# mouseHatbiggertest.net
KiCad netlist of a schematic drawn in EAGLE
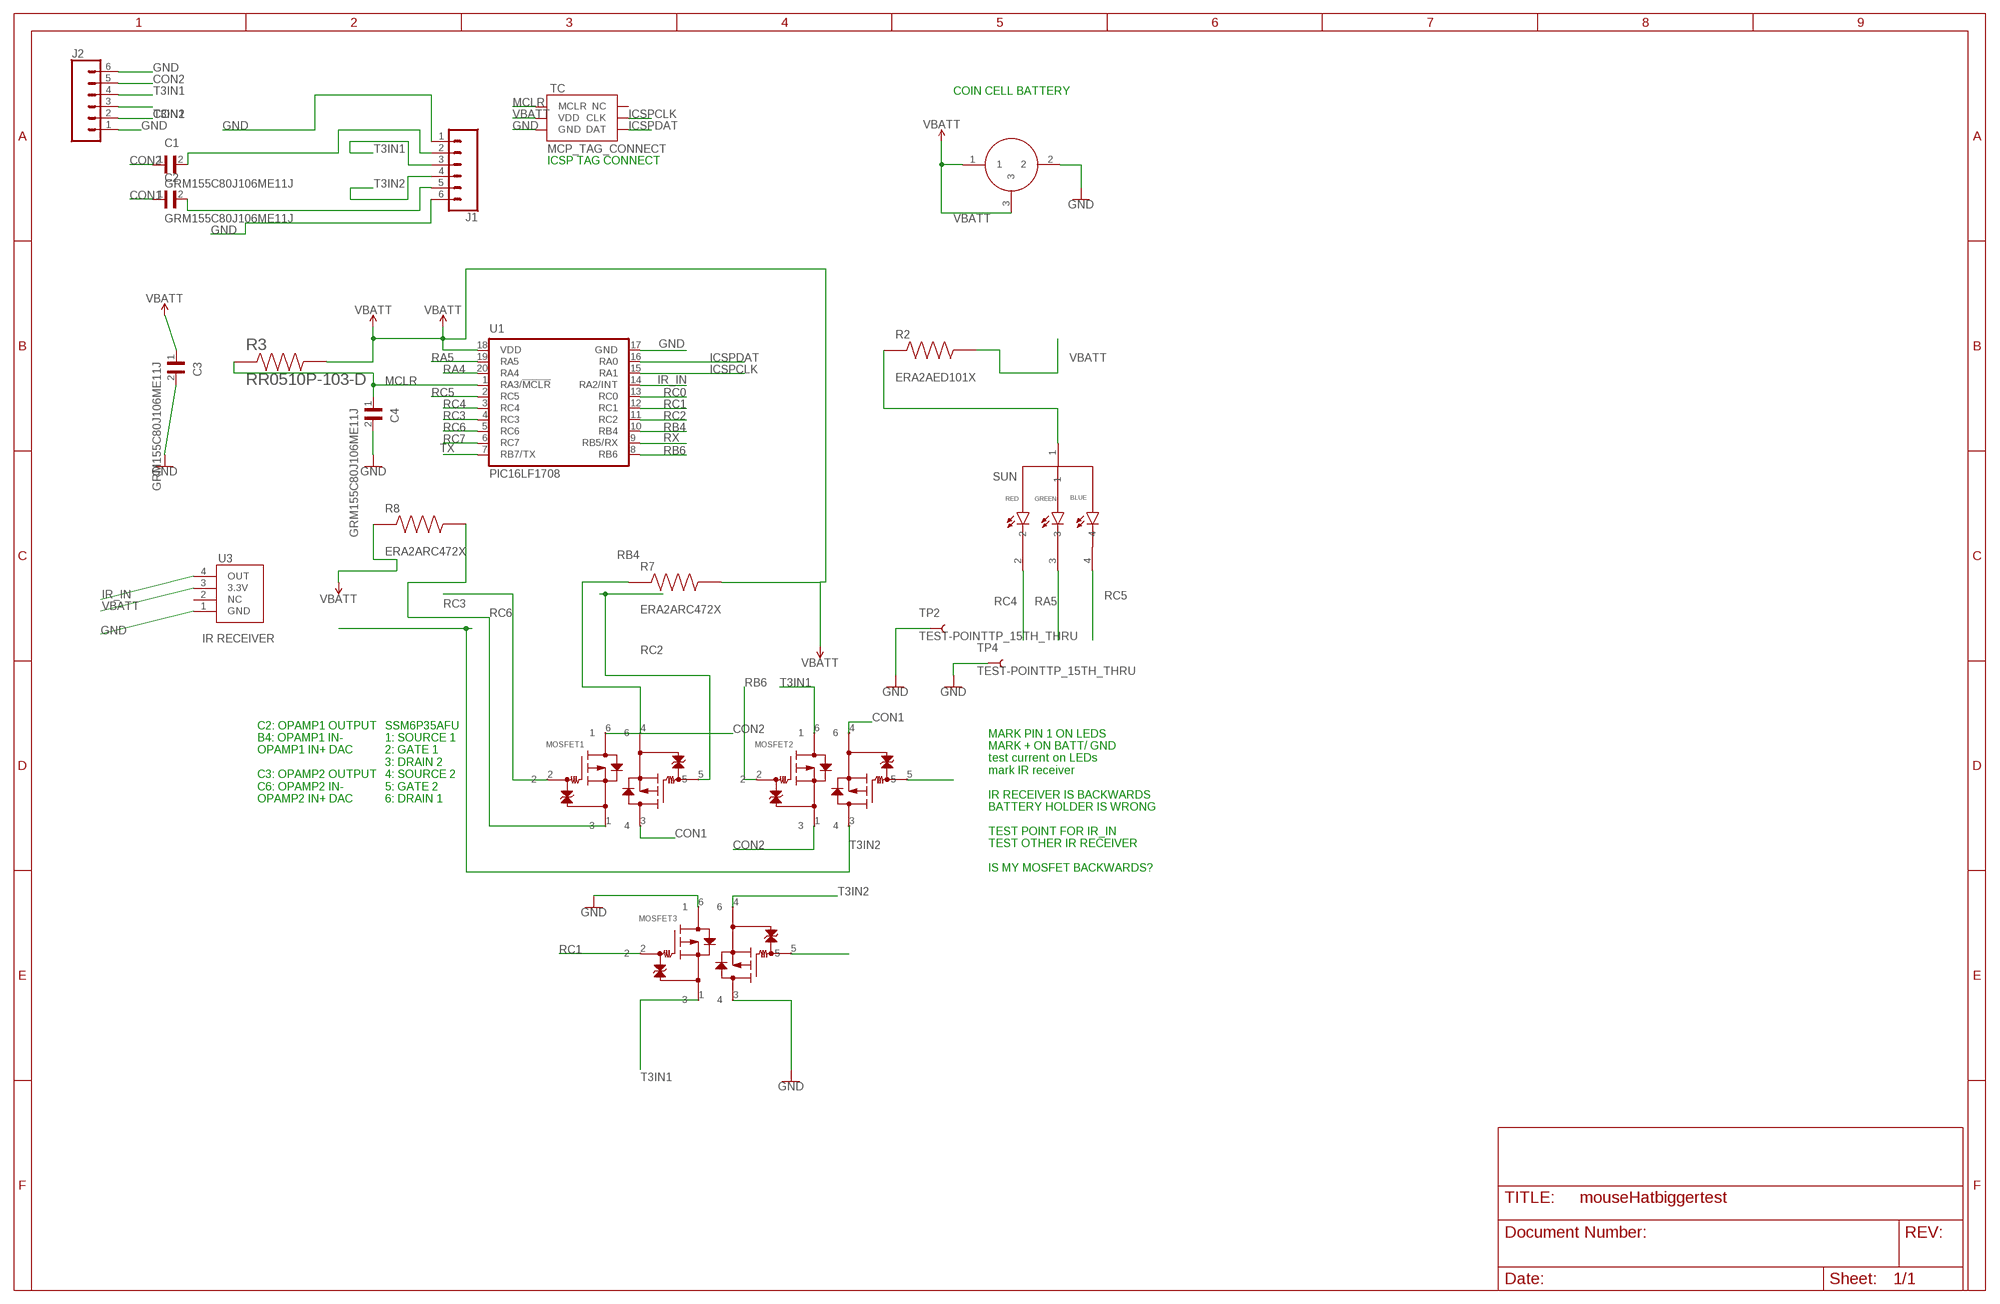
[diagram p0: schematic, sheet 1]

(export (version "E")
  (design (tool "Eeschema 10.0.6"))
  (components
    (comp (ref "C1")
      (value "GRM155C80J106ME11J")
      (footprint "eagle-import:CAPC1005X70N")
      (fields (field (name "DIGI-KEY_PART_NUMBER") "490-18210-1-ND") (field (name "MF") "Murata Electronics"))
      (libsource (lib "eagle-import") (part "GRM155C80J106ME11J"))
    )
    (comp (ref "C2")
      (value "GRM155C80J106ME11J")
      (footprint "eagle-import:CAPC1005X70N")
      (fields (field (name "DIGI-KEY_PART_NUMBER") "490-18210-1-ND") (field (name "MF") "Murata Electronics"))
      (libsource (lib "eagle-import") (part "GRM155C80J106ME11J"))
    )
    (comp (ref "C3")
      (value "GRM155C80J106ME11J")
      (footprint "eagle-import:CAPC1005X70N")
      (fields (field (name "DIGI-KEY_PART_NUMBER") "490-18210-1-ND") (field (name "MF") "Murata Electronics"))
      (libsource (lib "eagle-import") (part "GRM155C80J106ME11J"))
    )
    (comp (ref "C4")
      (value "GRM155C80J106ME11J")
      (footprint "eagle-import:CAPC1005X70N")
      (fields (field (name "DIGI-KEY_PART_NUMBER") "490-18210-1-ND") (field (name "MF") "Murata Electronics"))
      (libsource (lib "eagle-import") (part "GRM155C80J106ME11J"))
    )
    (comp (ref "J1")
      (value "CONN_06NO_SILK_FEMALE_PTH")
      (footprint "eagle-import:1X06_NO_SILK")
      (libsource (lib "eagle-import") (part "CONN_06NO_SILK_FEMALE_PTH"))
    )
    (comp (ref "J2")
      (value "CONN_06NO_SILK_FEMALE_PTH")
      (footprint "eagle-import:1X06_NO_SILK")
      (libsource (lib "eagle-import") (part "CONN_06NO_SILK_FEMALE_PTH"))
    )
    (comp (ref "MOSFET1")
      (value "SSM6P35AFE,LF")
      (footprint "eagle-import:ES6_TOS")
      (fields (field (name "COPYRIGHT") "Copyright (C) 2021 Ultra Librarian. All rights reserved."))
      (libsource (lib "eagle-import") (part "SSM6P35AFE,LF"))
    )
    (comp (ref "MOSFET2")
      (value "SSM6P35AFE,LF")
      (footprint "eagle-import:ES6_TOS")
      (fields (field (name "COPYRIGHT") "Copyright (C) 2021 Ultra Librarian. All rights reserved."))
      (libsource (lib "eagle-import") (part "SSM6P35AFE,LF"))
    )
    (comp (ref "MOSFET3")
      (value "SSM6P35AFE,LF")
      (footprint "eagle-import:ES6_TOS")
      (fields (field (name "COPYRIGHT") "Copyright (C) 2021 Ultra Librarian. All rights reserved."))
      (libsource (lib "eagle-import") (part "SSM6P35AFE,LF"))
    )
    (comp (ref "R2")
      (value "ERA2AED101X")
      (footprint "eagle-import:RES_ERA2AED101X")
      (fields (field (name "DIGI-KEY_PART_NUMBER") "P100DECT-ND") (field (name "MF") "Panasonic"))
      (libsource (lib "eagle-import") (part "ERA2AED101X"))
    )
    (comp (ref "R3")
      (value "RR0510P-103-D")
      (footprint "eagle-import:RESC1005X40N")
      (fields (field (name "DIGI-KEY_PART_NUMBER") "RR05P10.0KDCT-ND") (field (name "MF") "Susumu"))
      (libsource (lib "eagle-import") (part "RR0510P-103-D"))
    )
    (comp (ref "R7")
      (value "ERA2ARC472X")
      (footprint "eagle-import:RES_ERA2ARC472X")
      (fields (field (name "DIGI-KEY_PART_NUMBER") "P4.7KCQCT-ND") (field (name "MF") "Panasonic"))
      (libsource (lib "eagle-import") (part "ERA2ARC472X"))
    )
    (comp (ref "R8")
      (value "ERA2ARC472X")
      (footprint "eagle-import:RES_ERA2ARC472X")
      (fields (field (name "DIGI-KEY_PART_NUMBER") "P4.7KCQCT-ND") (field (name "MF") "Panasonic"))
      (libsource (lib "eagle-import") (part "ERA2ARC472X"))
    )
    (comp (ref "TC")
      (value "MCP_TAG_CONNECT")
      (footprint "eagle-import:TAG_CONNECT_MCP")
      (libsource (lib "eagle-import") (part "MCP_TAG_CONNECT"))
    )
    (comp (ref "TP2")
      (value "TEST-POINTTP_15TH_THRU")
      (footprint "eagle-import:TP_15TH")
      (libsource (lib "eagle-import") (part "TEST-POINTTP_15TH_THRU"))
    )
    (comp (ref "TP4")
      (value "TEST-POINTTP_15TH_THRU")
      (footprint "eagle-import:TP_15TH")
      (libsource (lib "eagle-import") (part "TEST-POINTTP_15TH_THRU"))
    )
    (comp (ref "U$2")
      (value "10MM_BATT_HOLDER")
      (footprint "eagle-import:10MM_BATT_HOLDER")
      (libsource (lib "eagle-import") (part "10MM_BATT_HOLDER"))
    )
    (comp (ref "U$6")
      (value "SUN")
      (footprint "eagle-import:LED_RGB_SUN")
      (libsource (lib "eagle-import") (part "LED_RGB_SUN"))
    )
    (comp (ref "U1")
      (value "PIC16LF1708")
      (footprint "eagle-import:QFN20")
      (libsource (lib "eagle-import") (part "PIC16LF1708QFN20"))
    )
    (comp (ref "U3")
      (value "IR RECEIVER")
      (footprint "eagle-import:TSOP6238")
      (libsource (lib "eagle-import") (part "TSOP6238"))
    )
  )
  (nets
    (net (code "1") (name "/CON1") (class "Default")
      (node (ref "C2") (pin "1") (pinfunction "1_1") (pintype "passive"))
      (node (ref "J2") (pin "2") (pinfunction "2_2") (pintype "passive"))
      (node (ref "MOSFET1") (pin "3") (pinfunction "4_3") (pintype "passive"))
      (node (ref "MOSFET2") (pin "4") (pinfunction "6_4") (pintype "passive"))
    )
    (net (code "2") (name "/CON2") (class "Default")
      (node (ref "C1") (pin "1") (pinfunction "1_1") (pintype "passive"))
      (node (ref "J2") (pin "5") (pinfunction "5_5") (pintype "passive"))
      (node (ref "MOSFET1") (pin "6") (pinfunction "1_6") (pintype "passive"))
      (node (ref "MOSFET2") (pin "1") (pinfunction "3_1") (pintype "passive"))
    )
    (net (code "3") (name "/ICSPCLK") (class "Default")
      (node (ref "TC") (pin "5") (pinfunction "CLK_5") (pintype "bidirectional"))
      (node (ref "U1") (pin "15") (pinfunction "RA1_15") (pintype "bidirectional"))
    )
    (net (code "4") (name "/ICSPDAT") (class "Default")
      (node (ref "TC") (pin "4") (pinfunction "DAT_4") (pintype "bidirectional"))
      (node (ref "U1") (pin "16") (pinfunction "RA0_16") (pintype "bidirectional"))
    )
    (net (code "5") (name "/IR_IN") (class "Default")
      (node (ref "U1") (pin "14") (pinfunction "RA2/INT_14") (pintype "bidirectional"))
      (node (ref "U3") (pin "4") (pinfunction "OUT_4") (pintype "bidirectional"))
    )
    (net (code "6") (name "/MCLR") (class "Default")
      (node (ref "C4") (pin "1") (pinfunction "1_1") (pintype "passive"))
      (node (ref "R3") (pin "1") (pinfunction "1_1") (pintype "passive"))
      (node (ref "TC") (pin "1") (pinfunction "MCLR_1") (pintype "bidirectional"))
      (node (ref "U1") (pin "1") (pinfunction "RA3/~{MCLR}_1") (pintype "input"))
    )
    (net (code "7") (name "/RA4") (class "Default")
      (node (ref "U1") (pin "20") (pinfunction "RA4_20") (pintype "bidirectional"))
    )
    (net (code "8") (name "/RA5") (class "Default")
      (node (ref "U$6") (pin "3") (pinfunction "3_3") (pintype "bidirectional"))
      (node (ref "U1") (pin "19") (pinfunction "RA5_19") (pintype "bidirectional"))
    )
    (net (code "9") (name "/RB4") (class "Default")
      (node (ref "MOSFET1") (pin "4") (pinfunction "6_4") (pintype "passive"))
      (node (ref "R7") (pin "1") (pinfunction "1_1") (pintype "passive"))
      (node (ref "U1") (pin "10") (pinfunction "RB4_10") (pintype "bidirectional"))
    )
    (net (code "10") (name "/RB6") (class "Default")
      (node (ref "MOSFET2") (pin "2") (pinfunction "2_2") (pintype "passive"))
      (node (ref "U1") (pin "8") (pinfunction "RB6_8") (pintype "bidirectional"))
    )
    (net (code "11") (name "/RC0") (class "Default")
      (node (ref "MOSFET2") (pin "5") (pinfunction "5_5") (pintype "passive"))
      (node (ref "U1") (pin "13") (pinfunction "RC0_13") (pintype "power_in"))
    )
    (net (code "12") (name "/RC1") (class "Default")
      (node (ref "MOSFET3") (pin "2") (pinfunction "2_2") (pintype "passive"))
      (node (ref "U1") (pin "12") (pinfunction "RC1_12") (pintype "power_in"))
    )
    (net (code "13") (name "/RC2") (class "Default")
      (node (ref "MOSFET1") (pin "5") (pinfunction "5_5") (pintype "passive"))
      (node (ref "U1") (pin "11") (pinfunction "RC2_11") (pintype "bidirectional"))
    )
    (net (code "14") (name "/RC3") (class "Default")
      (node (ref "MOSFET1") (pin "2") (pinfunction "2_2") (pintype "passive"))
      (node (ref "U1") (pin "4") (pinfunction "RC3_4") (pintype "bidirectional"))
    )
    (net (code "15") (name "/RC4") (class "Default")
      (node (ref "U$6") (pin "2") (pinfunction "2_2") (pintype "bidirectional"))
      (node (ref "U1") (pin "3") (pinfunction "RC4_3") (pintype "power_in"))
    )
    (net (code "16") (name "/RC5") (class "Default")
      (node (ref "U$6") (pin "4") (pinfunction "4_4") (pintype "bidirectional"))
      (node (ref "U1") (pin "2") (pinfunction "RC5_2") (pintype "power_in"))
    )
    (net (code "17") (name "/RC6") (class "Default")
      (node (ref "MOSFET1") (pin "1") (pinfunction "3_1") (pintype "passive"))
      (node (ref "R8") (pin "2") (pinfunction "2_2") (pintype "passive"))
      (node (ref "U1") (pin "5") (pinfunction "RC6_5") (pintype "bidirectional"))
    )
    (net (code "18") (name "/RC7") (class "Default")
      (node (ref "MOSFET3") (pin "5") (pinfunction "5_5") (pintype "passive"))
      (node (ref "U1") (pin "6") (pinfunction "RC7_6") (pintype "bidirectional"))
    )
    (net (code "19") (name "/RX") (class "Default")
      (node (ref "U1") (pin "9") (pinfunction "RB5/RX_9") (pintype "bidirectional"))
    )
    (net (code "20") (name "/T3IN1") (class "Default")
      (node (ref "J1") (pin "3") (pinfunction "3_3") (pintype "passive"))
      (node (ref "J2") (pin "4") (pinfunction "4_4") (pintype "passive"))
      (node (ref "MOSFET2") (pin "6") (pinfunction "1_6") (pintype "passive"))
      (node (ref "MOSFET3") (pin "1") (pinfunction "3_1") (pintype "passive"))
    )
    (net (code "21") (name "/T3IN2") (class "Default")
      (node (ref "J1") (pin "4") (pinfunction "4_4") (pintype "passive"))
      (node (ref "J2") (pin "3") (pinfunction "3_3") (pintype "passive"))
      (node (ref "MOSFET2") (pin "3") (pinfunction "4_3") (pintype "passive"))
      (node (ref "MOSFET3") (pin "4") (pinfunction "6_4") (pintype "passive"))
    )
    (net (code "22") (name "/TX") (class "Default")
      (node (ref "U1") (pin "7") (pinfunction "RB7/TX_7") (pintype "bidirectional"))
    )
    (net (code "23") (name "GND") (class "Default")
      (node (ref "C3") (pin "2") (pinfunction "2_2") (pintype "passive"))
      (node (ref "C4") (pin "2") (pinfunction "2_2") (pintype "passive"))
      (node (ref "J1") (pin "1") (pinfunction "1_1") (pintype "passive"))
      (node (ref "J1") (pin "6") (pinfunction "6_6") (pintype "passive"))
      (node (ref "J2") (pin "1") (pinfunction "1_1") (pintype "passive"))
      (node (ref "J2") (pin "6") (pinfunction "6_6") (pintype "passive"))
      (node (ref "MOSFET3") (pin "3") (pinfunction "4_3") (pintype "passive"))
      (node (ref "MOSFET3") (pin "6") (pinfunction "1_6") (pintype "passive"))
      (node (ref "TC") (pin "3") (pinfunction "GND_3") (pintype "bidirectional"))
      (node (ref "TP2") (pin "P$1") (pinfunction "1_P$1") (pintype "bidirectional"))
      (node (ref "TP4") (pin "P$1") (pinfunction "1_P$1") (pintype "bidirectional"))
      (node (ref "U$2") (pin "2") (pinfunction "2_2") (pintype "bidirectional"))
      (node (ref "U1") (pin "17") (pinfunction "GND_17") (pintype "bidirectional"))
      (node (ref "U3") (pin "1") (pinfunction "GND_1") (pintype "bidirectional"))
    )
    (net (code "24") (name "Net-(C1-Pad2)") (class "Default")
      (node (ref "C1") (pin "2") (pinfunction "2_2") (pintype "passive"))
      (node (ref "J1") (pin "2") (pinfunction "2_2") (pintype "passive"))
    )
    (net (code "25") (name "Net-(C2-Pad2)") (class "Default")
      (node (ref "C2") (pin "2") (pinfunction "2_2") (pintype "passive"))
      (node (ref "J1") (pin "5") (pinfunction "5_5") (pintype "passive"))
    )
    (net (code "26") (name "Net-(R2-Pad1)") (class "Default")
      (node (ref "R2") (pin "1") (pinfunction "1_1") (pintype "passive"))
      (node (ref "U$6") (pin "1") (pinfunction "1_1") (pintype "bidirectional"))
    )
    (net (code "27") (name "VBATT") (class "Default")
      (node (ref "C3") (pin "1") (pinfunction "1_1") (pintype "passive"))
      (node (ref "R2") (pin "2") (pinfunction "2_2") (pintype "passive"))
      (node (ref "R3") (pin "2") (pinfunction "2_2") (pintype "passive"))
      (node (ref "R7") (pin "2") (pinfunction "2_2") (pintype "passive"))
      (node (ref "R8") (pin "1") (pinfunction "1_1") (pintype "passive"))
      (node (ref "TC") (pin "2") (pinfunction "VDD_2") (pintype "bidirectional"))
      (node (ref "U$2") (pin "1") (pinfunction "1_1") (pintype "bidirectional"))
      (node (ref "U$2") (pin "3") (pinfunction "3_3") (pintype "bidirectional"))
      (node (ref "U1") (pin "18") (pinfunction "VDD_18") (pintype "bidirectional"))
      (node (ref "U3") (pin "3") (pinfunction "3.3V_3") (pintype "bidirectional"))
    )
    (net (code "28") (name "unconnected-(TC-NC-Pad6)") (class "Default")
      (node (ref "TC") (pin "6") (pinfunction "NC_6") (pintype "bidirectional"))
    )
    (net (code "29") (name "unconnected-(U3-NC-Pad2)") (class "Default")
      (node (ref "U3") (pin "2") (pinfunction "NC_2") (pintype "bidirectional"))
    )
  )
)
